# 1-Schematic_GPIO_WAVER_15PIN_V2.net
KiCad netlist of a schematic drawn in EasyEDA
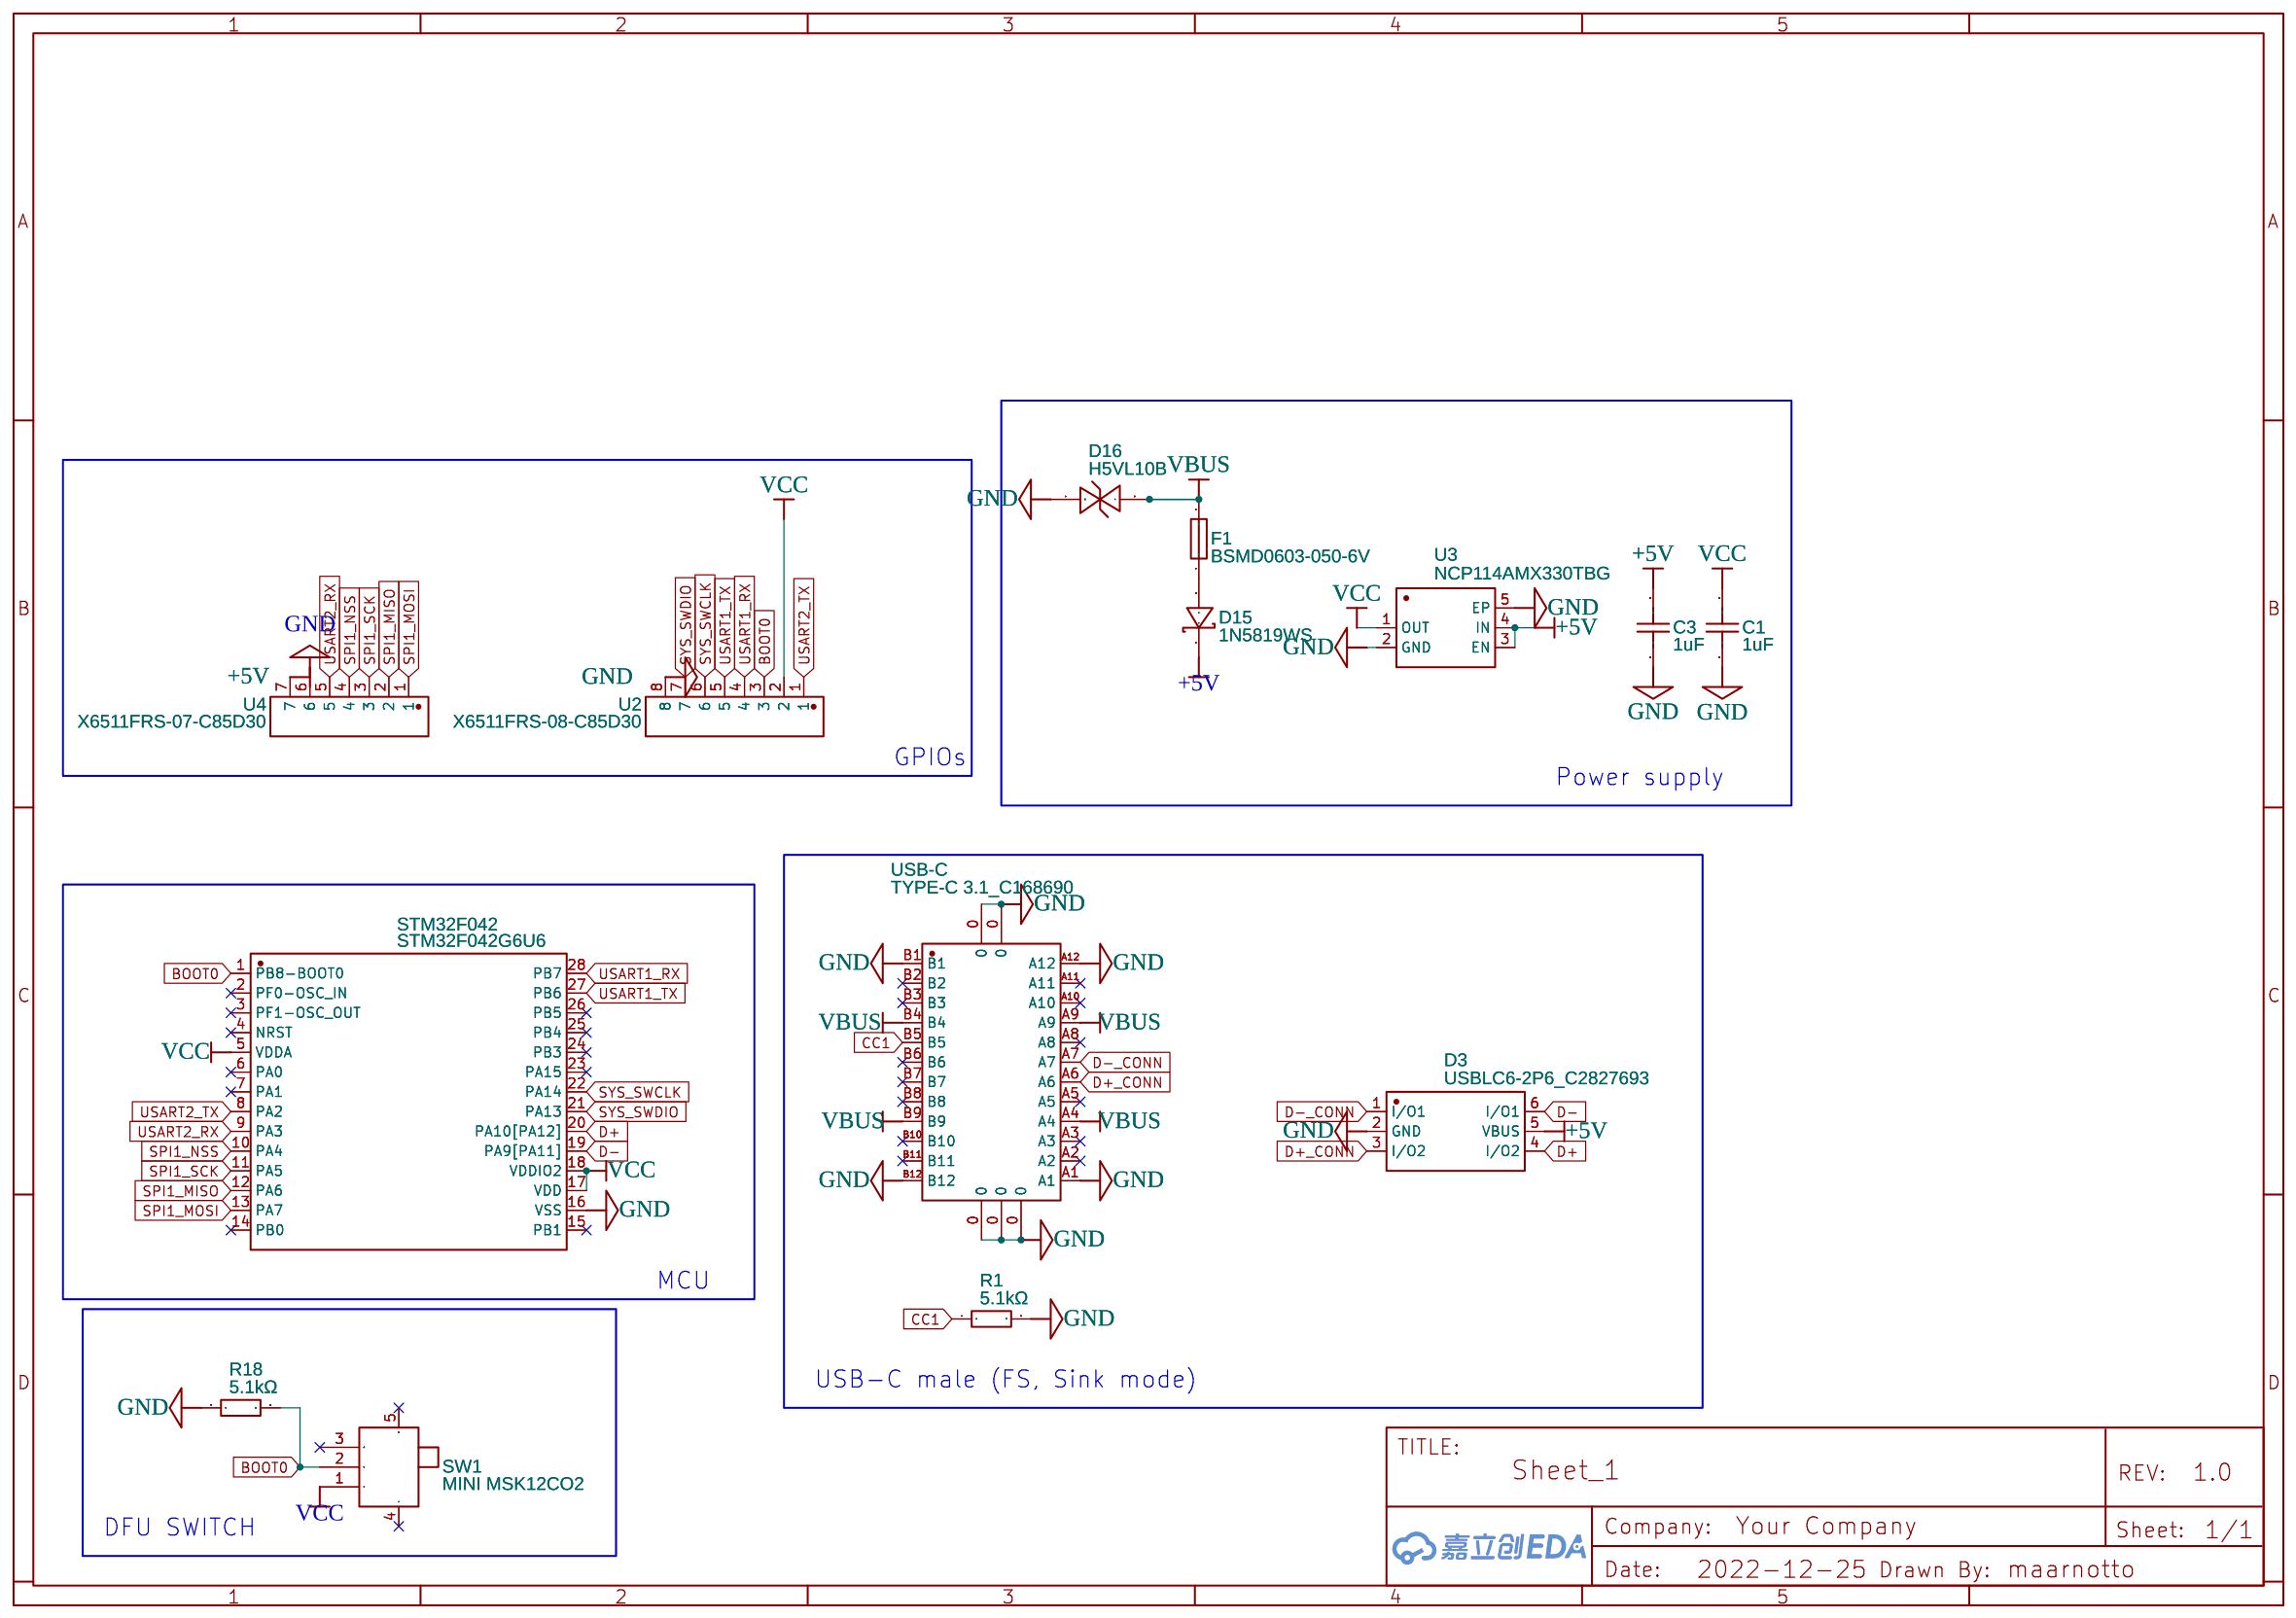
[diagram p0: schematic sheet]

(export (version "E")
  (design (tool "Eeschema 10.0.6"))
  (components
    (comp (ref "C1") (value "1uF") (libsource (lib "") (part "C_0603_US")))
    (comp (ref "C3") (value "1uF") (libsource (lib "") (part "C_0603_US")))
    (comp (ref "D3")
      (value "USBLC6-2P6_C2827693")
      (fields (field (name "Manufacturer Part") "USBLC6-2P6") (field (name "Manufacturer") "TECH PUBLIC(台舟)"))
      (libsource (lib "") (part "USBLC6-2P6_C2827693"))
    )
    (comp (ref "D15")
      (value "1N5819WS")
      (fields (field (name "Manufacturer") "Hottech(合科泰)"))
      (libsource (lib "") (part "1N5819WS"))
    )
    (comp (ref "D16")
      (value "H5VL10B")
      (fields (field (name "Manufacturer") "宏迦橙"))
      (libsource (lib "") (part "H5VL10B"))
    )
    (comp (ref "F1")
      (value "BSMD0603-050-6V")
      (fields (field (name "Manufacturer") "BHFUSE(佰宏)"))
      (libsource (lib "") (part "BSMD0603-050-6V"))
    )
    (comp (ref "R1")
      (value "5.1kΩ")
      (fields
        (field (name "Manufacturer Part") "0402WGF5101TCE")
        (field (name "Manufacturer") "UNI-ROYAL(厚声)")
      )
      (libsource (lib "") (part "0402WGF5101TCE"))
    )
    (comp (ref "R18")
      (value "5.1kΩ")
      (fields
        (field (name "Manufacturer Part") "0402WGF5101TCE")
        (field (name "Manufacturer") "UNI-ROYAL(厚声)")
      )
      (libsource (lib "") (part "0402WGF5101TCE"))
    )
    (comp (ref "STM32F042")
      (value "STM32F042G6U6")
      (fields (field (name "Manufacturer") "ST(意法半导体)"))
      (libsource (lib "") (part "STM32F042G6U6"))
    )
    (comp (ref "SW1")
      (value "MINI MSK12CO2")
      (fields (field (name "Manufacturer") "SHOU HAN(首韩)"))
      (libsource (lib "") (part "MINI MSK12CO2"))
    )
    (comp (ref "U2")
      (value "X6511FRS-08-C85D30")
      (fields (field (name "Manufacturer") "XKB Connectivity(中国星坤)"))
      (libsource (lib "") (part "X6511FRS-08-C85D30"))
    )
    (comp (ref "U3")
      (value "NCP114AMX330TBG")
      (fields (field (name "Manufacturer") "onsemi(安森美)"))
      (libsource (lib "") (part "NCP114AMX330TBG"))
    )
    (comp (ref "U4")
      (value "X6511FRS-07-C85D30")
      (fields (field (name "Manufacturer") "XKB Connectivity(中国星坤)"))
      (libsource (lib "") (part "X6511FRS-07-C85D30"))
    )
    (comp (ref "USB-C")
      (value "TYPE-C 3.1_C168690")
      (fields (field (name "Manufacturer Part") "918-118A2021Y40000") (field (name "Manufacturer") "精拓金"))
      (libsource (lib "") (part "TYPE-C 3.1_C168690"))
    )
  )
  (nets
    (net (code "1") (name "+5V") (class "Default")
      (node (ref "C3") (pin "2") (pinfunction "2_2") (pintype "unspecified"))
      (node (ref "D15") (pin "1") (pinfunction "K_1") (pintype "unspecified"))
      (node (ref "D3") (pin "5") (pinfunction "VBUS_5") (pintype "unspecified"))
      (node (ref "U3") (pin "3") (pinfunction "EN_3") (pintype "unspecified"))
      (node (ref "U3") (pin "4") (pinfunction "IN_4") (pintype "unspecified"))
      (node (ref "U4") (pin "7") (pinfunction "7_7") (pintype "unspecified"))
    )
    (net (code "2") (name "BOOT0") (class "Default")
      (node (ref "R18") (pin "2") (pinfunction "2_2") (pintype "input"))
      (node (ref "STM32F042") (pin "1") (pinfunction "PB8-BOOT0_1") (pintype "unspecified"))
      (node (ref "SW1") (pin "2") (pinfunction "2_2") (pintype "unspecified"))
      (node (ref "U2") (pin "3") (pinfunction "3_3") (pintype "unspecified"))
    )
    (net (code "3") (name "CC1") (class "Default")
      (node (ref "R1") (pin "1") (pinfunction "1_1") (pintype "input"))
      (node (ref "USB-C") (pin "B5") (pinfunction "B5_B5") (pintype "unspecified"))
    )
    (net (code "4") (name "D+") (class "Default")
      (node (ref "D3") (pin "4") (pinfunction "I/O2_4") (pintype "unspecified"))
      (node (ref "STM32F042") (pin "20") (pinfunction "PA10[PA12]_20") (pintype "unspecified"))
    )
    (net (code "5") (name "D+_CONN") (class "Default")
      (node (ref "D3") (pin "3") (pinfunction "I/O2_3") (pintype "unspecified"))
      (node (ref "USB-C") (pin "A6") (pinfunction "A6_A6") (pintype "unspecified"))
    )
    (net (code "6") (name "D-") (class "Default")
      (node (ref "D3") (pin "6") (pinfunction "I/O1_6") (pintype "unspecified"))
      (node (ref "STM32F042") (pin "19") (pinfunction "PA9[PA11]_19") (pintype "unspecified"))
    )
    (net (code "7") (name "D-_CONN") (class "Default")
      (node (ref "D3") (pin "1") (pinfunction "I/O1_1") (pintype "unspecified"))
      (node (ref "USB-C") (pin "A7") (pinfunction "A7_A7") (pintype "unspecified"))
    )
    (net (code "8") (name "GND") (class "Default")
      (node (ref "C1") (pin "1") (pinfunction "1_1") (pintype "unspecified"))
      (node (ref "C3") (pin "1") (pinfunction "1_1") (pintype "unspecified"))
      (node (ref "D16") (pin "1") (pinfunction "C_1") (pintype "unspecified"))
      (node (ref "D3") (pin "2") (pinfunction "GND_2") (pintype "unspecified"))
      (node (ref "R1") (pin "2") (pinfunction "2_2") (pintype "input"))
      (node (ref "R18") (pin "1") (pinfunction "1_1") (pintype "input"))
      (node (ref "STM32F042") (pin "16") (pinfunction "VSS_16") (pintype "unspecified"))
      (node (ref "U2") (pin "8") (pinfunction "8_8") (pintype "unspecified"))
      (node (ref "U3") (pin "2") (pinfunction "GND_2") (pintype "unspecified"))
      (node (ref "U3") (pin "5") (pinfunction "EP_5") (pintype "unspecified"))
      (node (ref "U4") (pin "6") (pinfunction "6_6") (pintype "unspecified"))
      (node (ref "USB-C") (pin "0") (pinfunction "0_0") (pintype "unspecified"))
      (node (ref "USB-C") (pin "A1") (pinfunction "A1_A1") (pintype "unspecified"))
      (node (ref "USB-C") (pin "A12") (pinfunction "A12_A12") (pintype "unspecified"))
      (node (ref "USB-C") (pin "B1") (pinfunction "B1_B1") (pintype "unspecified"))
      (node (ref "USB-C") (pin "B12") (pinfunction "B12_B12") (pintype "unspecified"))
    )
    (net (code "9") (name "Net-(D15-A)") (class "Default")
      (node (ref "D15") (pin "2") (pinfunction "A_2") (pintype "unspecified"))
      (node (ref "F1") (pin "1") (pinfunction "1_1") (pintype "unspecified"))
    )
    (net (code "10") (name "SPI1_MISO") (class "Default")
      (node (ref "STM32F042") (pin "12") (pinfunction "PA6_12") (pintype "unspecified"))
      (node (ref "U4") (pin "2") (pinfunction "2_2") (pintype "unspecified"))
    )
    (net (code "11") (name "SPI1_MOSI") (class "Default")
      (node (ref "STM32F042") (pin "13") (pinfunction "PA7_13") (pintype "unspecified"))
      (node (ref "U4") (pin "1") (pinfunction "1_1") (pintype "unspecified"))
    )
    (net (code "12") (name "SPI1_NSS") (class "Default")
      (node (ref "STM32F042") (pin "10") (pinfunction "PA4_10") (pintype "unspecified"))
      (node (ref "U4") (pin "4") (pinfunction "4_4") (pintype "unspecified"))
    )
    (net (code "13") (name "SPI1_SCK") (class "Default")
      (node (ref "STM32F042") (pin "11") (pinfunction "PA5_11") (pintype "unspecified"))
      (node (ref "U4") (pin "3") (pinfunction "3_3") (pintype "unspecified"))
    )
    (net (code "14") (name "SYS_SWCLK") (class "Default")
      (node (ref "STM32F042") (pin "22") (pinfunction "PA14_22") (pintype "unspecified"))
      (node (ref "U2") (pin "6") (pinfunction "6_6") (pintype "unspecified"))
    )
    (net (code "15") (name "SYS_SWDIO") (class "Default")
      (node (ref "STM32F042") (pin "21") (pinfunction "PA13_21") (pintype "unspecified"))
      (node (ref "U2") (pin "7") (pinfunction "7_7") (pintype "unspecified"))
    )
    (net (code "16") (name "USART1_RX") (class "Default")
      (node (ref "STM32F042") (pin "28") (pinfunction "PB7_28") (pintype "unspecified"))
      (node (ref "U2") (pin "4") (pinfunction "4_4") (pintype "unspecified"))
    )
    (net (code "17") (name "USART1_TX") (class "Default")
      (node (ref "STM32F042") (pin "27") (pinfunction "PB6_27") (pintype "unspecified"))
      (node (ref "U2") (pin "5") (pinfunction "5_5") (pintype "unspecified"))
    )
    (net (code "18") (name "USART2_RX") (class "Default")
      (node (ref "STM32F042") (pin "9") (pinfunction "PA3_9") (pintype "unspecified"))
      (node (ref "U4") (pin "5") (pinfunction "5_5") (pintype "unspecified"))
    )
    (net (code "19") (name "USART2_TX") (class "Default")
      (node (ref "STM32F042") (pin "8") (pinfunction "PA2_8") (pintype "unspecified"))
      (node (ref "U2") (pin "1") (pinfunction "1_1") (pintype "unspecified"))
    )
    (net (code "20") (name "VBUS") (class "Default")
      (node (ref "D16") (pin "2") (pinfunction "A_2") (pintype "unspecified"))
      (node (ref "F1") (pin "2") (pinfunction "2_2") (pintype "unspecified"))
      (node (ref "USB-C") (pin "A4") (pinfunction "A4_A4") (pintype "unspecified"))
      (node (ref "USB-C") (pin "A9") (pinfunction "A9_A9") (pintype "unspecified"))
      (node (ref "USB-C") (pin "B4") (pinfunction "B4_B4") (pintype "unspecified"))
      (node (ref "USB-C") (pin "B9") (pinfunction "B9_B9") (pintype "unspecified"))
    )
    (net (code "21") (name "VCC") (class "Default")
      (node (ref "C1") (pin "2") (pinfunction "2_2") (pintype "unspecified"))
      (node (ref "STM32F042") (pin "17") (pinfunction "VDD_17") (pintype "unspecified"))
      (node (ref "STM32F042") (pin "18") (pinfunction "VDDIO2_18") (pintype "unspecified"))
      (node (ref "STM32F042") (pin "5") (pinfunction "VDDA_5") (pintype "unspecified"))
      (node (ref "SW1") (pin "1") (pinfunction "1_1") (pintype "unspecified"))
      (node (ref "U2") (pin "2") (pinfunction "2_2") (pintype "unspecified"))
      (node (ref "U3") (pin "1") (pinfunction "OUT_1") (pintype "unspecified"))
    )
    (net (code "22") (name "unconnected-(STM32F042-NRST-Pad4)") (class "Default")
      (node (ref "STM32F042") (pin "4") (pinfunction "NRST_4") (pintype "unspecified+no_connect"))
    )
    (net (code "23") (name "unconnected-(STM32F042-PA0-Pad6)") (class "Default")
      (node (ref "STM32F042") (pin "6") (pinfunction "PA0_6") (pintype "unspecified+no_connect"))
    )
    (net (code "24") (name "unconnected-(STM32F042-PA1-Pad7)") (class "Default")
      (node (ref "STM32F042") (pin "7") (pinfunction "PA1_7") (pintype "unspecified+no_connect"))
    )
    (net (code "25") (name "unconnected-(STM32F042-PA15-Pad23)") (class "Default")
      (node (ref "STM32F042") (pin "23") (pinfunction "PA15_23") (pintype "unspecified+no_connect"))
    )
    (net (code "26") (name "unconnected-(STM32F042-PB0-Pad14)") (class "Default")
      (node (ref "STM32F042") (pin "14") (pinfunction "PB0_14") (pintype "unspecified+no_connect"))
    )
    (net (code "27") (name "unconnected-(STM32F042-PB1-Pad15)") (class "Default")
      (node (ref "STM32F042") (pin "15") (pinfunction "PB1_15") (pintype "unspecified+no_connect"))
    )
    (net (code "28") (name "unconnected-(STM32F042-PB3-Pad24)") (class "Default")
      (node (ref "STM32F042") (pin "24") (pinfunction "PB3_24") (pintype "unspecified+no_connect"))
    )
    (net (code "29") (name "unconnected-(STM32F042-PB4-Pad25)") (class "Default")
      (node (ref "STM32F042") (pin "25") (pinfunction "PB4_25") (pintype "unspecified+no_connect"))
    )
    (net (code "30") (name "unconnected-(STM32F042-PB5-Pad26)") (class "Default")
      (node (ref "STM32F042") (pin "26") (pinfunction "PB5_26") (pintype "unspecified+no_connect"))
    )
    (net (code "31") (name "unconnected-(STM32F042-PF0-OSC_IN-Pad2)") (class "Default")
      (node (ref "STM32F042") (pin "2") (pinfunction "PF0-OSC_IN_2") (pintype "unspecified+no_connect"))
    )
    (net (code "32") (name "unconnected-(STM32F042-PF1-OSC_OUT-Pad3)") (class "Default")
      (node (ref "STM32F042") (pin "3") (pinfunction "PF1-OSC_OUT_3") (pintype "unspecified+no_connect"))
    )
    (net (code "33") (name "unconnected-(SW1-Pad3)") (class "Default")
      (node (ref "SW1") (pin "3") (pinfunction "3_3") (pintype "unspecified+no_connect"))
    )
    (net (code "34") (name "unconnected-(SW1-Pad4)") (class "Default")
      (node (ref "SW1") (pin "4") (pinfunction "4_4") (pintype "unspecified+no_connect"))
    )
    (net (code "35") (name "unconnected-(SW1-Pad5)") (class "Default")
      (node (ref "SW1") (pin "5") (pinfunction "5_5") (pintype "unspecified+no_connect"))
    )
    (net (code "36") (name "unconnected-(USB-C-PadA2)") (class "Default")
      (node (ref "USB-C") (pin "A2") (pinfunction "A2_A2") (pintype "unspecified+no_connect"))
    )
    (net (code "37") (name "unconnected-(USB-C-PadA3)") (class "Default")
      (node (ref "USB-C") (pin "A3") (pinfunction "A3_A3") (pintype "unspecified+no_connect"))
    )
    (net (code "38") (name "unconnected-(USB-C-PadA5)") (class "Default")
      (node (ref "USB-C") (pin "A5") (pinfunction "A5_A5") (pintype "unspecified+no_connect"))
    )
    (net (code "39") (name "unconnected-(USB-C-PadA8)") (class "Default")
      (node (ref "USB-C") (pin "A8") (pinfunction "A8_A8") (pintype "unspecified+no_connect"))
    )
    (net (code "40") (name "unconnected-(USB-C-PadA10)") (class "Default")
      (node (ref "USB-C") (pin "A10") (pinfunction "A10_A10") (pintype "unspecified+no_connect"))
    )
    (net (code "41") (name "unconnected-(USB-C-PadA11)") (class "Default")
      (node (ref "USB-C") (pin "A11") (pinfunction "A11_A11") (pintype "unspecified+no_connect"))
    )
    (net (code "42") (name "unconnected-(USB-C-PadB2)") (class "Default")
      (node (ref "USB-C") (pin "B2") (pinfunction "B2_B2") (pintype "unspecified+no_connect"))
    )
    (net (code "43") (name "unconnected-(USB-C-PadB3)") (class "Default")
      (node (ref "USB-C") (pin "B3") (pinfunction "B3_B3") (pintype "unspecified+no_connect"))
    )
    (net (code "44") (name "unconnected-(USB-C-PadB6)") (class "Default")
      (node (ref "USB-C") (pin "B6") (pinfunction "B6_B6") (pintype "unspecified+no_connect"))
    )
    (net (code "45") (name "unconnected-(USB-C-PadB7)") (class "Default")
      (node (ref "USB-C") (pin "B7") (pinfunction "B7_B7") (pintype "unspecified+no_connect"))
    )
    (net (code "46") (name "unconnected-(USB-C-PadB8)") (class "Default")
      (node (ref "USB-C") (pin "B8") (pinfunction "B8_B8") (pintype "unspecified+no_connect"))
    )
    (net (code "47") (name "unconnected-(USB-C-PadB10)") (class "Default")
      (node (ref "USB-C") (pin "B10") (pinfunction "B10_B10") (pintype "unspecified+no_connect"))
    )
    (net (code "48") (name "unconnected-(USB-C-PadB11)") (class "Default")
      (node (ref "USB-C") (pin "B11") (pinfunction "B11_B11") (pintype "unspecified+no_connect"))
    )
  )
)
